# IOexpanderModule.net
KiCad netlist of a schematic drawn in EAGLE
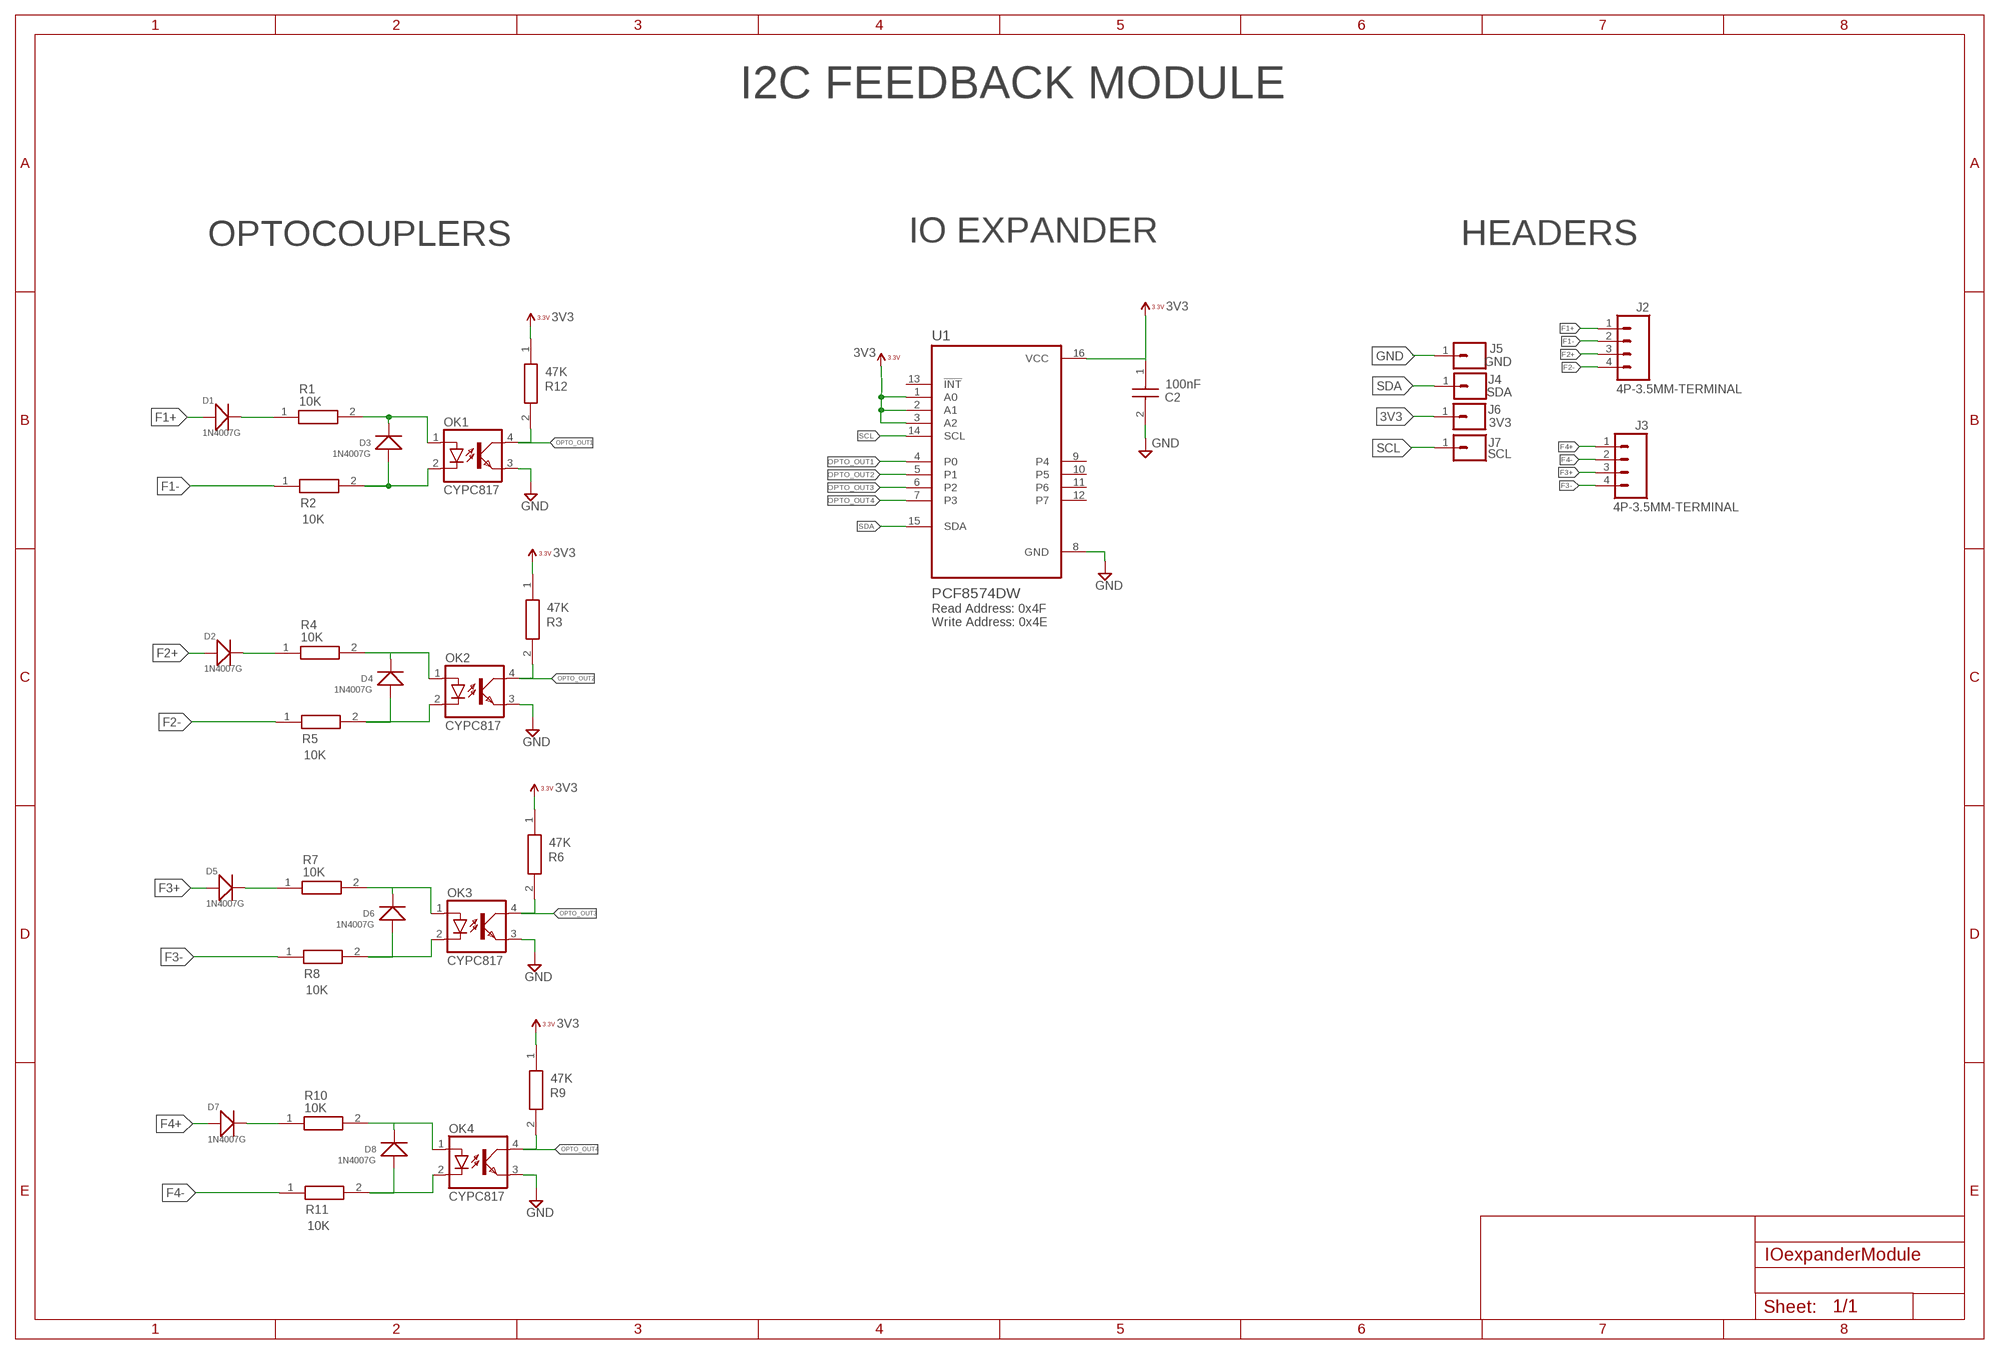
[diagram p0: schematic, sheet 1]

(export (version "E")
  (design (tool "Eeschema 10.0.6"))
  (components
    (comp (ref "C2")
      (value "100nF")
      (footprint "eagle-import:CAPC1005X55N")
      (fields (field (name "PARTNUMBER") "C0402C104K4RAC"))
      (libsource (lib "eagle-import") (part "C0402C104K4RAC"))
    )
    (comp (ref "D1")
      (value "1N4007G")
      (footprint "eagle-import:DO-214AC")
      (fields (field (name "PARTNUMBER") "S1M-13-F"))
      (libsource (lib "eagle-import") (part "SMD-DIODE-SCHOTTKY-40V-1A(DO-214AC)"))
    )
    (comp (ref "D2")
      (value "1N4007G")
      (footprint "eagle-import:DO-214AC")
      (fields (field (name "PARTNUMBER") "S1M-13-F"))
      (libsource (lib "eagle-import") (part "SMD-DIODE-SCHOTTKY-40V-1A(DO-214AC)"))
    )
    (comp (ref "D3")
      (value "1N4007G")
      (footprint "eagle-import:DO-214AC")
      (fields (field (name "PARTNUMBER") "S1M-13-F"))
      (libsource (lib "eagle-import") (part "SMD-DIODE-SCHOTTKY-40V-1A(DO-214AC)"))
    )
    (comp (ref "D4")
      (value "1N4007G")
      (footprint "eagle-import:DO-214AC")
      (fields (field (name "PARTNUMBER") "S1M-13-F"))
      (libsource (lib "eagle-import") (part "SMD-DIODE-SCHOTTKY-40V-1A(DO-214AC)"))
    )
    (comp (ref "D5")
      (value "1N4007G")
      (footprint "eagle-import:DO-214AC")
      (fields (field (name "PARTNUMBER") "S1M-13-F"))
      (libsource (lib "eagle-import") (part "SMD-DIODE-SCHOTTKY-40V-1A(DO-214AC)"))
    )
    (comp (ref "D6")
      (value "1N4007G")
      (footprint "eagle-import:DO-214AC")
      (fields (field (name "PARTNUMBER") "S1M-13-F"))
      (libsource (lib "eagle-import") (part "SMD-DIODE-SCHOTTKY-40V-1A(DO-214AC)"))
    )
    (comp (ref "D7")
      (value "1N4007G")
      (footprint "eagle-import:DO-214AC")
      (fields (field (name "PARTNUMBER") "S1M-13-F"))
      (libsource (lib "eagle-import") (part "SMD-DIODE-SCHOTTKY-40V-1A(DO-214AC)"))
    )
    (comp (ref "D8")
      (value "1N4007G")
      (footprint "eagle-import:DO-214AC")
      (fields (field (name "PARTNUMBER") "S1M-13-F"))
      (libsource (lib "eagle-import") (part "SMD-DIODE-SCHOTTKY-40V-1A(DO-214AC)"))
    )
    (comp (ref "J2")
      (value "4P-3.5MM-TERMINAL")
      (footprint "eagle-import:HDRVR4W80P350_1X4_1540X690X920B")
      (fields
        (field (name "PARTNUMBER") "DB2EVC-3.5-4P-GN")
        (field (name "PARTNUMBER_1") "DB2EVC-3.5-4P-GN")
        (field (name "PARTNUMBER2") "KF2EDGV-3.5-4P")
        (field (name "PARTNUMBER3") "395016004")
        (field (name "PARTNUMBER4") "284514-4")
      )
      (libsource (lib "eagle-import") (part "TERMINAL-PLUG-4P-3,5TERMINAL-3.5-4P"))
    )
    (comp (ref "J3")
      (value "4P-3.5MM-TERMINAL")
      (footprint "eagle-import:HDRVR4W80P350_1X4_1540X690X920B")
      (fields (field (name "PARTNUMBER") "DB2EVC-3.5-4P-GN"))
      (libsource (lib "eagle-import") (part "TERMINAL-PLUG-4P-3,5TERMINAL-3.5-4P"))
    )
    (comp (ref "J4")
      (value "SDA")
      (footprint "eagle-import:1X01")
      (fields (field (name "PARTNUMBER") "YELLOW 24AWG WIRE 150MM"))
      (libsource (lib "eagle-import") (part "CONN_01_PAD"))
    )
    (comp (ref "J5")
      (value "GND")
      (footprint "eagle-import:1X01")
      (fields (field (name "PARTNUMBER") "BLACK 24AWG WIRE 150MM"))
      (libsource (lib "eagle-import") (part "CONN_01_PAD"))
    )
    (comp (ref "J6")
      (value "3V3")
      (footprint "eagle-import:1X01")
      (fields (field (name "PARTNUMBER") "RED 24AWG WIRE 150MM"))
      (libsource (lib "eagle-import") (part "CONN_01_PAD"))
    )
    (comp (ref "J7")
      (value "SCL")
      (footprint "eagle-import:1X01")
      (fields (field (name "PARTNUMBER") "GREEN 24AWG WIRE 150MM"))
      (libsource (lib "eagle-import") (part "CONN_01_PAD"))
    )
    (comp (ref "OK1")
      (value "CYPC817")
      (footprint "eagle-import:DIL4-SMD")
      (fields (field (name "PARTNUMBER") "CYPC817(C-TP2)"))
      (libsource (lib "eagle-import") (part "LTV816S"))
    )
    (comp (ref "OK2")
      (value "CYPC817")
      (footprint "eagle-import:DIL4-SMD")
      (fields (field (name "PARTNUMBER") "CYPC817(C-TP2)"))
      (libsource (lib "eagle-import") (part "LTV816S"))
    )
    (comp (ref "OK3")
      (value "CYPC817")
      (footprint "eagle-import:DIL4-SMD")
      (fields (field (name "PARTNUMBER") "CYPC817(C-TP2)"))
      (libsource (lib "eagle-import") (part "LTV816S"))
    )
    (comp (ref "OK4")
      (value "CYPC817")
      (footprint "eagle-import:DIL4-SMD")
      (fields (field (name "PARTNUMBER") "CYPC817(C-TP2)"))
      (libsource (lib "eagle-import") (part "LTV816S"))
    )
    (comp (ref "R1")
      (value "10K")
      (footprint "eagle-import:ERJP06D_1000V")
      (fields (field (name "PARTNUMBER") "ERJ-P06J103V"))
      (libsource (lib "eagle-import") (part "ERJ-P06J103V"))
    )
    (comp (ref "R2")
      (value "10K")
      (footprint "eagle-import:ERJP06D_1000V")
      (fields (field (name "PARTNUMBER") "ERJ-P06J103V"))
      (libsource (lib "eagle-import") (part "ERJ-P06J103V"))
    )
    (comp (ref "R3")
      (value "47K")
      (footprint "eagle-import:ERJ2RKD1004X")
      (fields (field (name "PARTNUMBER") "ERJ-2RKF4702X"))
      (libsource (lib "eagle-import") (part "ERJ-2RKF4702X"))
    )
    (comp (ref "R4")
      (value "10K")
      (footprint "eagle-import:ERJP06D_1000V")
      (fields (field (name "PARTNUMBER") "ERJ-P06J103V"))
      (libsource (lib "eagle-import") (part "ERJ-P06J103V"))
    )
    (comp (ref "R5")
      (value "10K")
      (footprint "eagle-import:ERJP06D_1000V")
      (fields (field (name "PARTNUMBER") "ERJ-P06J103V"))
      (libsource (lib "eagle-import") (part "ERJ-P06J103V"))
    )
    (comp (ref "R6")
      (value "47K")
      (footprint "eagle-import:ERJ2RKD1004X")
      (fields (field (name "PARTNUMBER") "ERJ-2RKF4702X"))
      (libsource (lib "eagle-import") (part "ERJ-2RKF4702X"))
    )
    (comp (ref "R7")
      (value "10K")
      (footprint "eagle-import:ERJP06D_1000V")
      (fields (field (name "PARTNUMBER") "ERJ-P06J103V"))
      (libsource (lib "eagle-import") (part "ERJ-P06J103V"))
    )
    (comp (ref "R8")
      (value "10K")
      (footprint "eagle-import:ERJP06D_1000V")
      (fields (field (name "PARTNUMBER") "ERJ-P06J103V"))
      (libsource (lib "eagle-import") (part "ERJ-P06J103V"))
    )
    (comp (ref "R9")
      (value "47K")
      (footprint "eagle-import:ERJ2RKD1004X")
      (fields (field (name "PARTNUMBER") "ERJ-2RKF4702X"))
      (libsource (lib "eagle-import") (part "ERJ-2RKF4702X"))
    )
    (comp (ref "R10")
      (value "10K")
      (footprint "eagle-import:ERJP06D_1000V")
      (fields (field (name "PARTNUMBER") "ERJ-P06J103V"))
      (libsource (lib "eagle-import") (part "ERJ-P06J103V"))
    )
    (comp (ref "R11")
      (value "10K")
      (footprint "eagle-import:ERJP06D_1000V")
      (fields (field (name "PARTNUMBER") "ERJ-P06J103V"))
      (libsource (lib "eagle-import") (part "ERJ-P06J103V"))
    )
    (comp (ref "R12")
      (value "47K")
      (footprint "eagle-import:ERJ2RKD1004X")
      (fields (field (name "PARTNUMBER") "ERJ-2RKF4702X"))
      (libsource (lib "eagle-import") (part "ERJ-2RKF4702X"))
    )
    (comp (ref "U1")
      (value "PCF8574DW")
      (footprint "eagle-import:SOIC127P1030X265-16N")
      (fields (field (name "PARTNUMBER") "PCF8574DWR"))
      (libsource (lib "eagle-import") (part "PCF8574DW"))
    )
  )
  (nets
    (net (code "1") (name "3V3") (class "Default")
      (node (ref "C2") (pin "1") (pinfunction "1_1") (pintype "bidirectional"))
      (node (ref "J6") (pin "1") (pinfunction "1_1") (pintype "passive"))
      (node (ref "R12") (pin "1") (pinfunction "1_1") (pintype "bidirectional"))
      (node (ref "R3") (pin "1") (pinfunction "1_1") (pintype "bidirectional"))
      (node (ref "R6") (pin "1") (pinfunction "1_1") (pintype "bidirectional"))
      (node (ref "R9") (pin "1") (pinfunction "1_1") (pintype "bidirectional"))
      (node (ref "U1") (pin "1") (pinfunction "A0_1") (pintype "input"))
      (node (ref "U1") (pin "16") (pinfunction "VCC_16") (pintype "power_in"))
      (node (ref "U1") (pin "2") (pinfunction "A1_2") (pintype "input"))
      (node (ref "U1") (pin "3") (pinfunction "A2_3") (pintype "input"))
    )
    (net (code "2") (name "F1+") (class "Default")
      (node (ref "D1") (pin "1") (pinfunction "+_1") (pintype "passive"))
      (node (ref "J2") (pin "1") (pinfunction "1_1") (pintype "passive"))
    )
    (net (code "3") (name "F1-") (class "Default")
      (node (ref "J2") (pin "2") (pinfunction "2_2") (pintype "passive"))
      (node (ref "R2") (pin "1") (pinfunction "1_1") (pintype "bidirectional"))
    )
    (net (code "4") (name "F2+") (class "Default")
      (node (ref "D2") (pin "1") (pinfunction "+_1") (pintype "passive"))
      (node (ref "J2") (pin "3") (pinfunction "3_3") (pintype "passive"))
    )
    (net (code "5") (name "F2-") (class "Default")
      (node (ref "J2") (pin "4") (pinfunction "4_4") (pintype "passive"))
      (node (ref "R5") (pin "1") (pinfunction "1_1") (pintype "bidirectional"))
    )
    (net (code "6") (name "F3+") (class "Default")
      (node (ref "D5") (pin "1") (pinfunction "+_1") (pintype "passive"))
      (node (ref "J3") (pin "3") (pinfunction "3_3") (pintype "passive"))
    )
    (net (code "7") (name "F3-") (class "Default")
      (node (ref "J3") (pin "4") (pinfunction "4_4") (pintype "passive"))
      (node (ref "R8") (pin "1") (pinfunction "1_1") (pintype "bidirectional"))
    )
    (net (code "8") (name "F4+") (class "Default")
      (node (ref "D7") (pin "1") (pinfunction "+_1") (pintype "passive"))
      (node (ref "J3") (pin "1") (pinfunction "1_1") (pintype "passive"))
    )
    (net (code "9") (name "F4-") (class "Default")
      (node (ref "J3") (pin "2") (pinfunction "2_2") (pintype "passive"))
      (node (ref "R11") (pin "1") (pinfunction "1_1") (pintype "bidirectional"))
    )
    (net (code "10") (name "GND") (class "Default")
      (node (ref "C2") (pin "2") (pinfunction "2_2") (pintype "bidirectional"))
      (node (ref "J5") (pin "1") (pinfunction "1_1") (pintype "passive"))
      (node (ref "OK1") (pin "3") (pinfunction "EMIT_3") (pintype "passive"))
      (node (ref "OK2") (pin "3") (pinfunction "EMIT_3") (pintype "passive"))
      (node (ref "OK3") (pin "3") (pinfunction "EMIT_3") (pintype "passive"))
      (node (ref "OK4") (pin "3") (pinfunction "EMIT_3") (pintype "passive"))
      (node (ref "U1") (pin "8") (pinfunction "GND_8") (pintype "power_in"))
    )
    (net (code "11") (name "Net-(D1--)") (class "Default")
      (node (ref "D1") (pin "2") (pinfunction "-_2") (pintype "passive"))
      (node (ref "R1") (pin "1") (pinfunction "1_1") (pintype "bidirectional"))
    )
    (net (code "12") (name "Net-(D2--)") (class "Default")
      (node (ref "D2") (pin "2") (pinfunction "-_2") (pintype "passive"))
      (node (ref "R4") (pin "1") (pinfunction "1_1") (pintype "bidirectional"))
    )
    (net (code "13") (name "Net-(D3-+)") (class "Default")
      (node (ref "D3") (pin "1") (pinfunction "+_1") (pintype "passive"))
      (node (ref "OK1") (pin "2") (pinfunction "C_2") (pintype "passive"))
      (node (ref "R2") (pin "2") (pinfunction "2_2") (pintype "bidirectional"))
    )
    (net (code "14") (name "Net-(D3--)") (class "Default")
      (node (ref "D3") (pin "2") (pinfunction "-_2") (pintype "passive"))
      (node (ref "OK1") (pin "1") (pinfunction "A_1") (pintype "passive"))
      (node (ref "R1") (pin "2") (pinfunction "2_2") (pintype "bidirectional"))
    )
    (net (code "15") (name "Net-(D4-+)") (class "Default")
      (node (ref "D4") (pin "1") (pinfunction "+_1") (pintype "passive"))
      (node (ref "OK2") (pin "2") (pinfunction "C_2") (pintype "passive"))
      (node (ref "R5") (pin "2") (pinfunction "2_2") (pintype "bidirectional"))
    )
    (net (code "16") (name "Net-(D4--)") (class "Default")
      (node (ref "D4") (pin "2") (pinfunction "-_2") (pintype "passive"))
      (node (ref "OK2") (pin "1") (pinfunction "A_1") (pintype "passive"))
      (node (ref "R4") (pin "2") (pinfunction "2_2") (pintype "bidirectional"))
    )
    (net (code "17") (name "Net-(D5--)") (class "Default")
      (node (ref "D5") (pin "2") (pinfunction "-_2") (pintype "passive"))
      (node (ref "R7") (pin "1") (pinfunction "1_1") (pintype "bidirectional"))
    )
    (net (code "18") (name "Net-(D6-+)") (class "Default")
      (node (ref "D6") (pin "1") (pinfunction "+_1") (pintype "passive"))
      (node (ref "OK3") (pin "2") (pinfunction "C_2") (pintype "passive"))
      (node (ref "R8") (pin "2") (pinfunction "2_2") (pintype "bidirectional"))
    )
    (net (code "19") (name "Net-(D6--)") (class "Default")
      (node (ref "D6") (pin "2") (pinfunction "-_2") (pintype "passive"))
      (node (ref "OK3") (pin "1") (pinfunction "A_1") (pintype "passive"))
      (node (ref "R7") (pin "2") (pinfunction "2_2") (pintype "bidirectional"))
    )
    (net (code "20") (name "Net-(D7--)") (class "Default")
      (node (ref "D7") (pin "2") (pinfunction "-_2") (pintype "passive"))
      (node (ref "R10") (pin "1") (pinfunction "1_1") (pintype "bidirectional"))
    )
    (net (code "21") (name "Net-(D8-+)") (class "Default")
      (node (ref "D8") (pin "1") (pinfunction "+_1") (pintype "passive"))
      (node (ref "OK4") (pin "2") (pinfunction "C_2") (pintype "passive"))
      (node (ref "R11") (pin "2") (pinfunction "2_2") (pintype "bidirectional"))
    )
    (net (code "22") (name "Net-(D8--)") (class "Default")
      (node (ref "D8") (pin "2") (pinfunction "-_2") (pintype "passive"))
      (node (ref "OK4") (pin "1") (pinfunction "A_1") (pintype "passive"))
      (node (ref "R10") (pin "2") (pinfunction "2_2") (pintype "bidirectional"))
    )
    (net (code "23") (name "OPTO_OUT1") (class "Default")
      (node (ref "OK1") (pin "4") (pinfunction "COL_4") (pintype "passive"))
      (node (ref "R12") (pin "2") (pinfunction "2_2") (pintype "bidirectional"))
      (node (ref "U1") (pin "4") (pinfunction "P0_4") (pintype "bidirectional"))
    )
    (net (code "24") (name "OPTO_OUT2") (class "Default")
      (node (ref "OK2") (pin "4") (pinfunction "COL_4") (pintype "passive"))
      (node (ref "R3") (pin "2") (pinfunction "2_2") (pintype "bidirectional"))
      (node (ref "U1") (pin "5") (pinfunction "P1_5") (pintype "bidirectional"))
    )
    (net (code "25") (name "OPTO_OUT3") (class "Default")
      (node (ref "OK3") (pin "4") (pinfunction "COL_4") (pintype "passive"))
      (node (ref "R6") (pin "2") (pinfunction "2_2") (pintype "bidirectional"))
      (node (ref "U1") (pin "6") (pinfunction "P2_6") (pintype "bidirectional"))
    )
    (net (code "26") (name "OPTO_OUT4") (class "Default")
      (node (ref "OK4") (pin "4") (pinfunction "COL_4") (pintype "passive"))
      (node (ref "R9") (pin "2") (pinfunction "2_2") (pintype "bidirectional"))
      (node (ref "U1") (pin "7") (pinfunction "P3_7") (pintype "bidirectional"))
    )
    (net (code "27") (name "SCL") (class "Default")
      (node (ref "J7") (pin "1") (pinfunction "1_1") (pintype "passive"))
      (node (ref "U1") (pin "14") (pinfunction "SCL_14") (pintype "input"))
    )
    (net (code "28") (name "SDA") (class "Default")
      (node (ref "J4") (pin "1") (pinfunction "1_1") (pintype "passive"))
      (node (ref "U1") (pin "15") (pinfunction "SDA_15") (pintype "bidirectional"))
    )
    (net (code "29") (name "unconnected-(U1-P4-Pad9)") (class "Default")
      (node (ref "U1") (pin "9") (pinfunction "P4_9") (pintype "bidirectional"))
    )
    (net (code "30") (name "unconnected-(U1-P5-Pad10)") (class "Default")
      (node (ref "U1") (pin "10") (pinfunction "P5_10") (pintype "bidirectional"))
    )
    (net (code "31") (name "unconnected-(U1-P6-Pad11)") (class "Default")
      (node (ref "U1") (pin "11") (pinfunction "P6_11") (pintype "bidirectional"))
    )
    (net (code "32") (name "unconnected-(U1-P7-Pad12)") (class "Default")
      (node (ref "U1") (pin "12") (pinfunction "P7_12") (pintype "bidirectional"))
    )
    (net (code "33") (name "unconnected-(U1-~{INT}-Pad13)") (class "Default")
      (node (ref "U1") (pin "13") (pinfunction "~{INT}_13") (pintype "input"))
    )
  )
)
